# imu.net
KiCad netlist of a schematic drawn in EAGLE
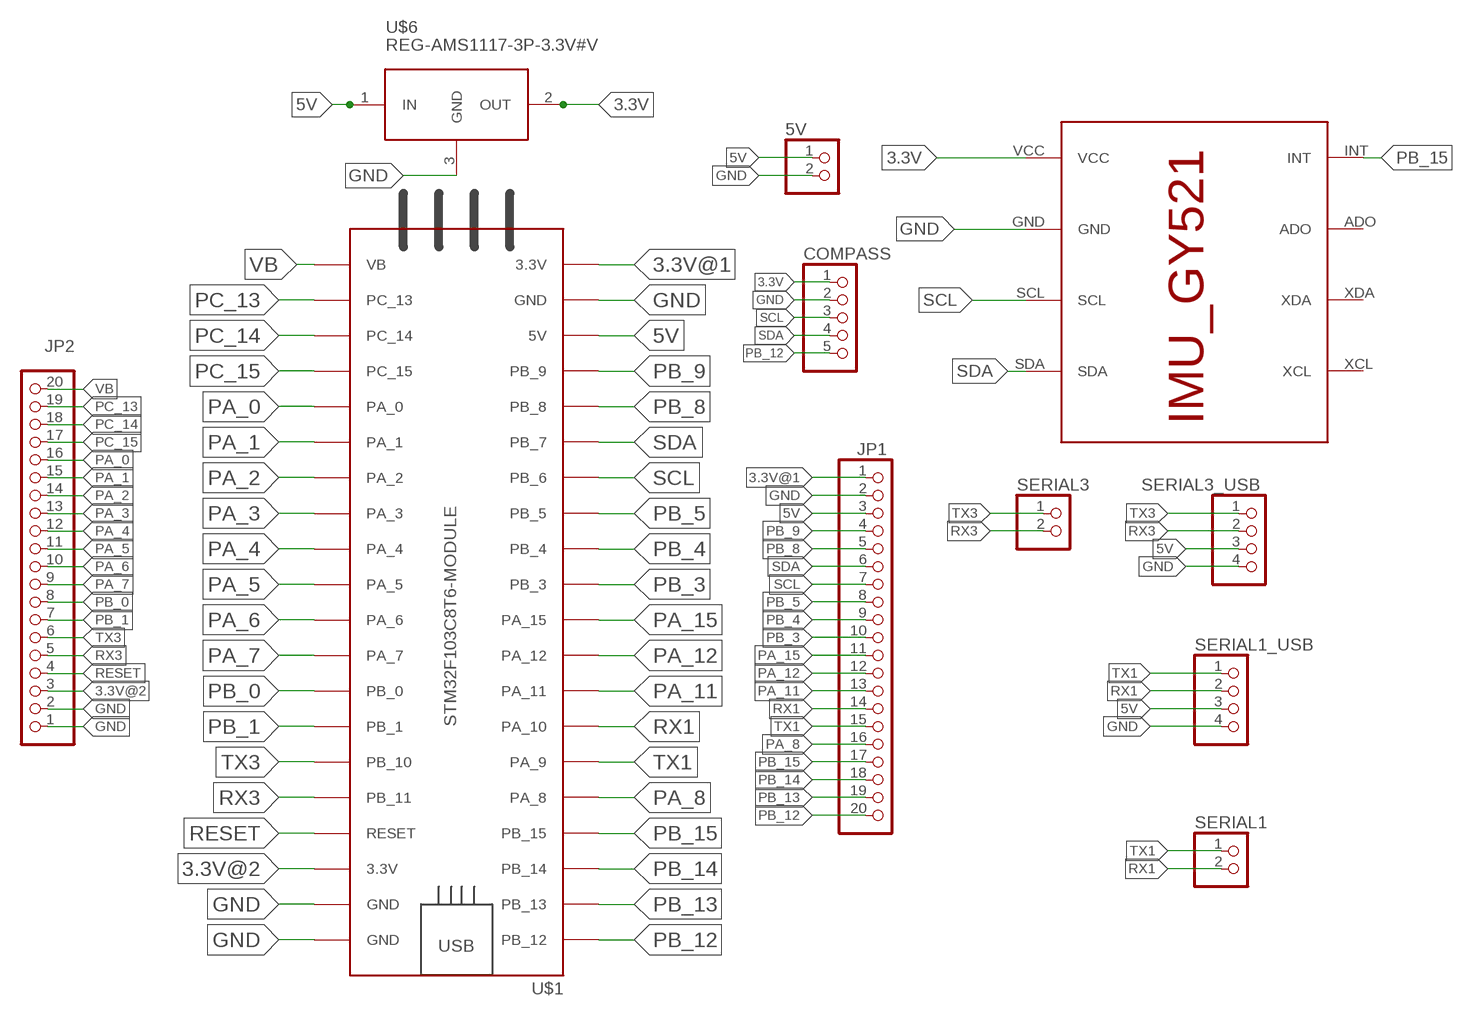
[diagram p0: schematic, sheet 1]

(export (version "E")
  (design (tool "Eeschema 10.0.6"))
  (components
    (comp (ref "5V")
      (value "PINHD-2_DATA")
      (footprint "eagle-import:1X02_DATA")
      (libsource (lib "eagle-import") (part "PINHD-2_DATA"))
    )
    (comp (ref "COMPASS")
      (value "PINHD-1X5")
      (footprint "eagle-import:1X05")
      (libsource (lib "eagle-import") (part "PINHD-1X5"))
    )
    (comp (ref "JP1")
      (value "PINHD-1X20")
      (footprint "eagle-import:1X20")
      (libsource (lib "eagle-import") (part "PINHD-1X20"))
    )
    (comp (ref "JP2")
      (value "PINHD-1X20")
      (footprint "eagle-import:1X20")
      (libsource (lib "eagle-import") (part "PINHD-1X20"))
    )
    (comp (ref "SERIAL1")
      (value "PINHD-2_DATA")
      (footprint "eagle-import:1X02_DATA")
      (libsource (lib "eagle-import") (part "PINHD-2_DATA"))
    )
    (comp (ref "SERIAL1_USB")
      (value "PINHD-4_DATA")
      (footprint "eagle-import:1X04_DATA")
      (libsource (lib "eagle-import") (part "PINHD-4_DATA"))
    )
    (comp (ref "SERIAL3")
      (value "PINHD-2_DATA")
      (footprint "eagle-import:1X02_DATA")
      (libsource (lib "eagle-import") (part "PINHD-2_DATA"))
    )
    (comp (ref "SERIAL3_USB")
      (value "PINHD-4_DATA")
      (footprint "eagle-import:1X04_DATA")
      (libsource (lib "eagle-import") (part "PINHD-4_DATA"))
    )
    (comp (ref "U$1")
      (value "STM32F103C8T6-MODULE")
      (footprint "eagle-import:STM32F103C8T6-MODULE")
      (libsource (lib "eagle-import") (part "STM32F103C8T6-MODULE"))
    )
    (comp (ref "U$2")
      (value "IMU_ROBOCON_GY521")
      (footprint "eagle-import:IMU_GY521")
      (libsource (lib "eagle-import") (part "IMU_ROBOCON_GY521"))
    )
    (comp (ref "U$6")
      (value "REG-AMS1117-3P-3.3V#V")
      (footprint "eagle-import:REG-AMS1117-3P#V")
      (libsource (lib "eagle-import") (part "REG-AMS1117-3P-#V3.3V"))
    )
  )
  (nets
    (net (code "1") (name "3.3V") (class "Default")
      (node (ref "COMPASS") (pin "1") (pinfunction "1_1") (pintype "passive"))
      (node (ref "U$2") (pin "VCC") (pinfunction "VCC_VCC") (pintype "bidirectional"))
      (node (ref "U$6") (pin "2") (pinfunction "OUT_2") (pintype "bidirectional"))
    )
    (net (code "2") (name "3.3V@1") (class "Default")
      (node (ref "JP1") (pin "1") (pinfunction "1_1") (pintype "passive"))
      (node (ref "U$1") (pin "3.3V_1") (pinfunction "3.3V_3.3V_1") (pintype "bidirectional"))
    )
    (net (code "3") (name "3.3V@2") (class "Default")
      (node (ref "JP2") (pin "3") (pinfunction "3_3") (pintype "passive"))
      (node (ref "U$1") (pin "3.3V_2") (pinfunction "3.3V_3.3V_2") (pintype "bidirectional"))
    )
    (net (code "4") (name "5V") (class "Default")
      (node (ref "5V") (pin "1") (pinfunction "1_1") (pintype "passive"))
      (node (ref "JP1") (pin "3") (pinfunction "3_3") (pintype "passive"))
      (node (ref "SERIAL1_USB") (pin "3") (pinfunction "3_3") (pintype "passive"))
      (node (ref "SERIAL3_USB") (pin "3") (pinfunction "3_3") (pintype "passive"))
      (node (ref "U$1") (pin "5V") (pinfunction "5V_5V") (pintype "bidirectional"))
      (node (ref "U$6") (pin "1") (pinfunction "IN_1") (pintype "bidirectional"))
    )
    (net (code "5") (name "GND") (class "Default")
      (node (ref "5V") (pin "2") (pinfunction "2_2") (pintype "passive"))
      (node (ref "COMPASS") (pin "2") (pinfunction "2_2") (pintype "passive"))
      (node (ref "JP1") (pin "2") (pinfunction "2_2") (pintype "passive"))
      (node (ref "JP2") (pin "1") (pinfunction "1_1") (pintype "passive"))
      (node (ref "JP2") (pin "2") (pinfunction "2_2") (pintype "passive"))
      (node (ref "SERIAL1_USB") (pin "4") (pinfunction "4_4") (pintype "passive"))
      (node (ref "SERIAL3_USB") (pin "4") (pinfunction "4_4") (pintype "passive"))
      (node (ref "U$1") (pin "GND_1") (pinfunction "GND_GND_1") (pintype "bidirectional"))
      (node (ref "U$1") (pin "GND_2") (pinfunction "GND_GND_2") (pintype "bidirectional"))
      (node (ref "U$1") (pin "GND_3") (pinfunction "GND_GND_3") (pintype "power_in"))
      (node (ref "U$2") (pin "GND") (pinfunction "GND_GND") (pintype "bidirectional"))
      (node (ref "U$6") (pin "3") (pinfunction "GND_3") (pintype "bidirectional"))
    )
    (net (code "6") (name "PA_0") (class "Default")
      (node (ref "JP2") (pin "16") (pinfunction "16_16") (pintype "passive"))
      (node (ref "U$1") (pin "PA_0") (pinfunction "PA_0_PA_0") (pintype "bidirectional"))
    )
    (net (code "7") (name "PA_1") (class "Default")
      (node (ref "JP2") (pin "15") (pinfunction "15_15") (pintype "passive"))
      (node (ref "U$1") (pin "PA_1") (pinfunction "PA_1_PA_1") (pintype "bidirectional"))
    )
    (net (code "8") (name "PA_2") (class "Default")
      (node (ref "JP2") (pin "14") (pinfunction "14_14") (pintype "passive"))
      (node (ref "U$1") (pin "PA_2") (pinfunction "PA_2_PA_2") (pintype "bidirectional"))
    )
    (net (code "9") (name "PA_3") (class "Default")
      (node (ref "JP2") (pin "13") (pinfunction "13_13") (pintype "passive"))
      (node (ref "U$1") (pin "PA_3") (pinfunction "PA_3_PA_3") (pintype "bidirectional"))
    )
    (net (code "10") (name "PA_4") (class "Default")
      (node (ref "JP2") (pin "12") (pinfunction "12_12") (pintype "passive"))
      (node (ref "U$1") (pin "PA_4") (pinfunction "PA_4_PA_4") (pintype "bidirectional"))
    )
    (net (code "11") (name "PA_5") (class "Default")
      (node (ref "JP2") (pin "11") (pinfunction "11_11") (pintype "passive"))
      (node (ref "U$1") (pin "PA_5") (pinfunction "PA_5_PA_5") (pintype "bidirectional"))
    )
    (net (code "12") (name "PA_6") (class "Default")
      (node (ref "JP2") (pin "10") (pinfunction "10_10") (pintype "passive"))
      (node (ref "U$1") (pin "PA_6") (pinfunction "PA_6_PA_6") (pintype "bidirectional"))
    )
    (net (code "13") (name "PA_7") (class "Default")
      (node (ref "JP2") (pin "9") (pinfunction "9_9") (pintype "passive"))
      (node (ref "U$1") (pin "PA_7") (pinfunction "PA_7_PA_7") (pintype "bidirectional"))
    )
    (net (code "14") (name "PA_8") (class "Default")
      (node (ref "JP1") (pin "16") (pinfunction "16_16") (pintype "passive"))
      (node (ref "U$1") (pin "PA_8") (pinfunction "PA_8_PA_8") (pintype "bidirectional"))
    )
    (net (code "15") (name "PA_11") (class "Default")
      (node (ref "JP1") (pin "13") (pinfunction "13_13") (pintype "passive"))
      (node (ref "U$1") (pin "PA_11") (pinfunction "PA_11_PA_11") (pintype "bidirectional"))
    )
    (net (code "16") (name "PA_12") (class "Default")
      (node (ref "JP1") (pin "12") (pinfunction "12_12") (pintype "passive"))
      (node (ref "U$1") (pin "PA_12") (pinfunction "PA_12_PA_12") (pintype "bidirectional"))
    )
    (net (code "17") (name "PA_15") (class "Default")
      (node (ref "JP1") (pin "11") (pinfunction "11_11") (pintype "passive"))
      (node (ref "U$1") (pin "PA_15") (pinfunction "PA_15_PA_15") (pintype "bidirectional"))
    )
    (net (code "18") (name "PB_0") (class "Default")
      (node (ref "JP2") (pin "8") (pinfunction "8_8") (pintype "passive"))
      (node (ref "U$1") (pin "PB_0") (pinfunction "PB_0_PB_0") (pintype "bidirectional"))
    )
    (net (code "19") (name "PB_1") (class "Default")
      (node (ref "JP2") (pin "7") (pinfunction "7_7") (pintype "passive"))
      (node (ref "U$1") (pin "PB_1") (pinfunction "PB_1_PB_1") (pintype "bidirectional"))
    )
    (net (code "20") (name "PB_3") (class "Default")
      (node (ref "JP1") (pin "10") (pinfunction "10_10") (pintype "passive"))
      (node (ref "U$1") (pin "PB_3") (pinfunction "PB_3_PB_3") (pintype "bidirectional"))
    )
    (net (code "21") (name "PB_4") (class "Default")
      (node (ref "JP1") (pin "9") (pinfunction "9_9") (pintype "passive"))
      (node (ref "U$1") (pin "PB_4") (pinfunction "PB_4_PB_4") (pintype "bidirectional"))
    )
    (net (code "22") (name "PB_5") (class "Default")
      (node (ref "JP1") (pin "8") (pinfunction "8_8") (pintype "passive"))
      (node (ref "U$1") (pin "PB_5") (pinfunction "PB_5_PB_5") (pintype "bidirectional"))
    )
    (net (code "23") (name "PB_8") (class "Default")
      (node (ref "JP1") (pin "5") (pinfunction "5_5") (pintype "passive"))
      (node (ref "U$1") (pin "PB_8") (pinfunction "PB_8_PB_8") (pintype "bidirectional"))
    )
    (net (code "24") (name "PB_9") (class "Default")
      (node (ref "JP1") (pin "4") (pinfunction "4_4") (pintype "passive"))
      (node (ref "U$1") (pin "PB_9") (pinfunction "PB_9_PB_9") (pintype "bidirectional"))
    )
    (net (code "25") (name "PB_12") (class "Default")
      (node (ref "COMPASS") (pin "5") (pinfunction "5_5") (pintype "passive"))
      (node (ref "JP1") (pin "20") (pinfunction "20_20") (pintype "passive"))
      (node (ref "U$1") (pin "PB_12") (pinfunction "PB_12_PB_12") (pintype "bidirectional"))
    )
    (net (code "26") (name "PB_13") (class "Default")
      (node (ref "JP1") (pin "19") (pinfunction "19_19") (pintype "passive"))
      (node (ref "U$1") (pin "PB_13") (pinfunction "PB_13_PB_13") (pintype "bidirectional"))
    )
    (net (code "27") (name "PB_14") (class "Default")
      (node (ref "JP1") (pin "18") (pinfunction "18_18") (pintype "passive"))
      (node (ref "U$1") (pin "PB_14") (pinfunction "PB_14_PB_14") (pintype "bidirectional"))
    )
    (net (code "28") (name "PB_15") (class "Default")
      (node (ref "JP1") (pin "17") (pinfunction "17_17") (pintype "passive"))
      (node (ref "U$1") (pin "PB_15") (pinfunction "PB_15_PB_15") (pintype "bidirectional"))
      (node (ref "U$2") (pin "INT") (pinfunction "INT_INT") (pintype "bidirectional"))
    )
    (net (code "29") (name "PC_13") (class "Default")
      (node (ref "JP2") (pin "19") (pinfunction "19_19") (pintype "passive"))
      (node (ref "U$1") (pin "PC_13") (pinfunction "PC_13_PC_13") (pintype "bidirectional"))
    )
    (net (code "30") (name "PC_14") (class "Default")
      (node (ref "JP2") (pin "18") (pinfunction "18_18") (pintype "passive"))
      (node (ref "U$1") (pin "PC_14") (pinfunction "PC_14_PC_14") (pintype "bidirectional"))
    )
    (net (code "31") (name "PC_15") (class "Default")
      (node (ref "JP2") (pin "17") (pinfunction "17_17") (pintype "passive"))
      (node (ref "U$1") (pin "PC_15") (pinfunction "PC_15_PC_15") (pintype "bidirectional"))
    )
    (net (code "32") (name "RESET") (class "Default")
      (node (ref "JP2") (pin "4") (pinfunction "4_4") (pintype "passive"))
      (node (ref "U$1") (pin "RESET") (pinfunction "RESET_RESET") (pintype "bidirectional"))
    )
    (net (code "33") (name "RX1") (class "Default")
      (node (ref "JP1") (pin "14") (pinfunction "14_14") (pintype "passive"))
      (node (ref "SERIAL1") (pin "2") (pinfunction "2_2") (pintype "passive"))
      (node (ref "SERIAL1_USB") (pin "2") (pinfunction "2_2") (pintype "passive"))
      (node (ref "U$1") (pin "PA_10") (pinfunction "PA_10_PA_10") (pintype "bidirectional"))
    )
    (net (code "34") (name "RX3") (class "Default")
      (node (ref "JP2") (pin "5") (pinfunction "5_5") (pintype "passive"))
      (node (ref "SERIAL3") (pin "2") (pinfunction "2_2") (pintype "passive"))
      (node (ref "SERIAL3_USB") (pin "2") (pinfunction "2_2") (pintype "passive"))
      (node (ref "U$1") (pin "PB_11") (pinfunction "PB_11_PB_11") (pintype "bidirectional"))
    )
    (net (code "35") (name "SCL") (class "Default")
      (node (ref "COMPASS") (pin "3") (pinfunction "3_3") (pintype "passive"))
      (node (ref "JP1") (pin "7") (pinfunction "7_7") (pintype "passive"))
      (node (ref "U$1") (pin "PB_6") (pinfunction "PB_6_PB_6") (pintype "bidirectional"))
      (node (ref "U$2") (pin "SCL") (pinfunction "SCL_SCL") (pintype "bidirectional"))
    )
    (net (code "36") (name "SDA") (class "Default")
      (node (ref "COMPASS") (pin "4") (pinfunction "4_4") (pintype "passive"))
      (node (ref "JP1") (pin "6") (pinfunction "6_6") (pintype "passive"))
      (node (ref "U$1") (pin "PB_7") (pinfunction "PB_7_PB_7") (pintype "bidirectional"))
      (node (ref "U$2") (pin "SDA") (pinfunction "SDA_SDA") (pintype "bidirectional"))
    )
    (net (code "37") (name "TX1") (class "Default")
      (node (ref "JP1") (pin "15") (pinfunction "15_15") (pintype "passive"))
      (node (ref "SERIAL1") (pin "1") (pinfunction "1_1") (pintype "passive"))
      (node (ref "SERIAL1_USB") (pin "1") (pinfunction "1_1") (pintype "passive"))
      (node (ref "U$1") (pin "PA_9") (pinfunction "PA_9_PA_9") (pintype "bidirectional"))
    )
    (net (code "38") (name "TX3") (class "Default")
      (node (ref "JP2") (pin "6") (pinfunction "6_6") (pintype "passive"))
      (node (ref "SERIAL3") (pin "1") (pinfunction "1_1") (pintype "passive"))
      (node (ref "SERIAL3_USB") (pin "1") (pinfunction "1_1") (pintype "passive"))
      (node (ref "U$1") (pin "PB_10") (pinfunction "PB_10_PB_10") (pintype "bidirectional"))
    )
    (net (code "39") (name "VB") (class "Default")
      (node (ref "JP2") (pin "20") (pinfunction "20_20") (pintype "passive"))
      (node (ref "U$1") (pin "VB") (pinfunction "VB_VB") (pintype "bidirectional"))
    )
    (net (code "40") (name "unconnected-(U$2-PadADO)") (class "Default")
      (node (ref "U$2") (pin "ADO") (pinfunction "ADO_ADO") (pintype "bidirectional"))
    )
    (net (code "41") (name "unconnected-(U$2-PadXCL)") (class "Default")
      (node (ref "U$2") (pin "XCL") (pinfunction "XCL_XCL") (pintype "bidirectional"))
    )
    (net (code "42") (name "unconnected-(U$2-PadXDA)") (class "Default")
      (node (ref "U$2") (pin "XDA") (pinfunction "XDA_XDA") (pintype "bidirectional"))
    )
  )
)
